# CCM_0010.net
KiCad netlist of a schematic drawn in EAGLE
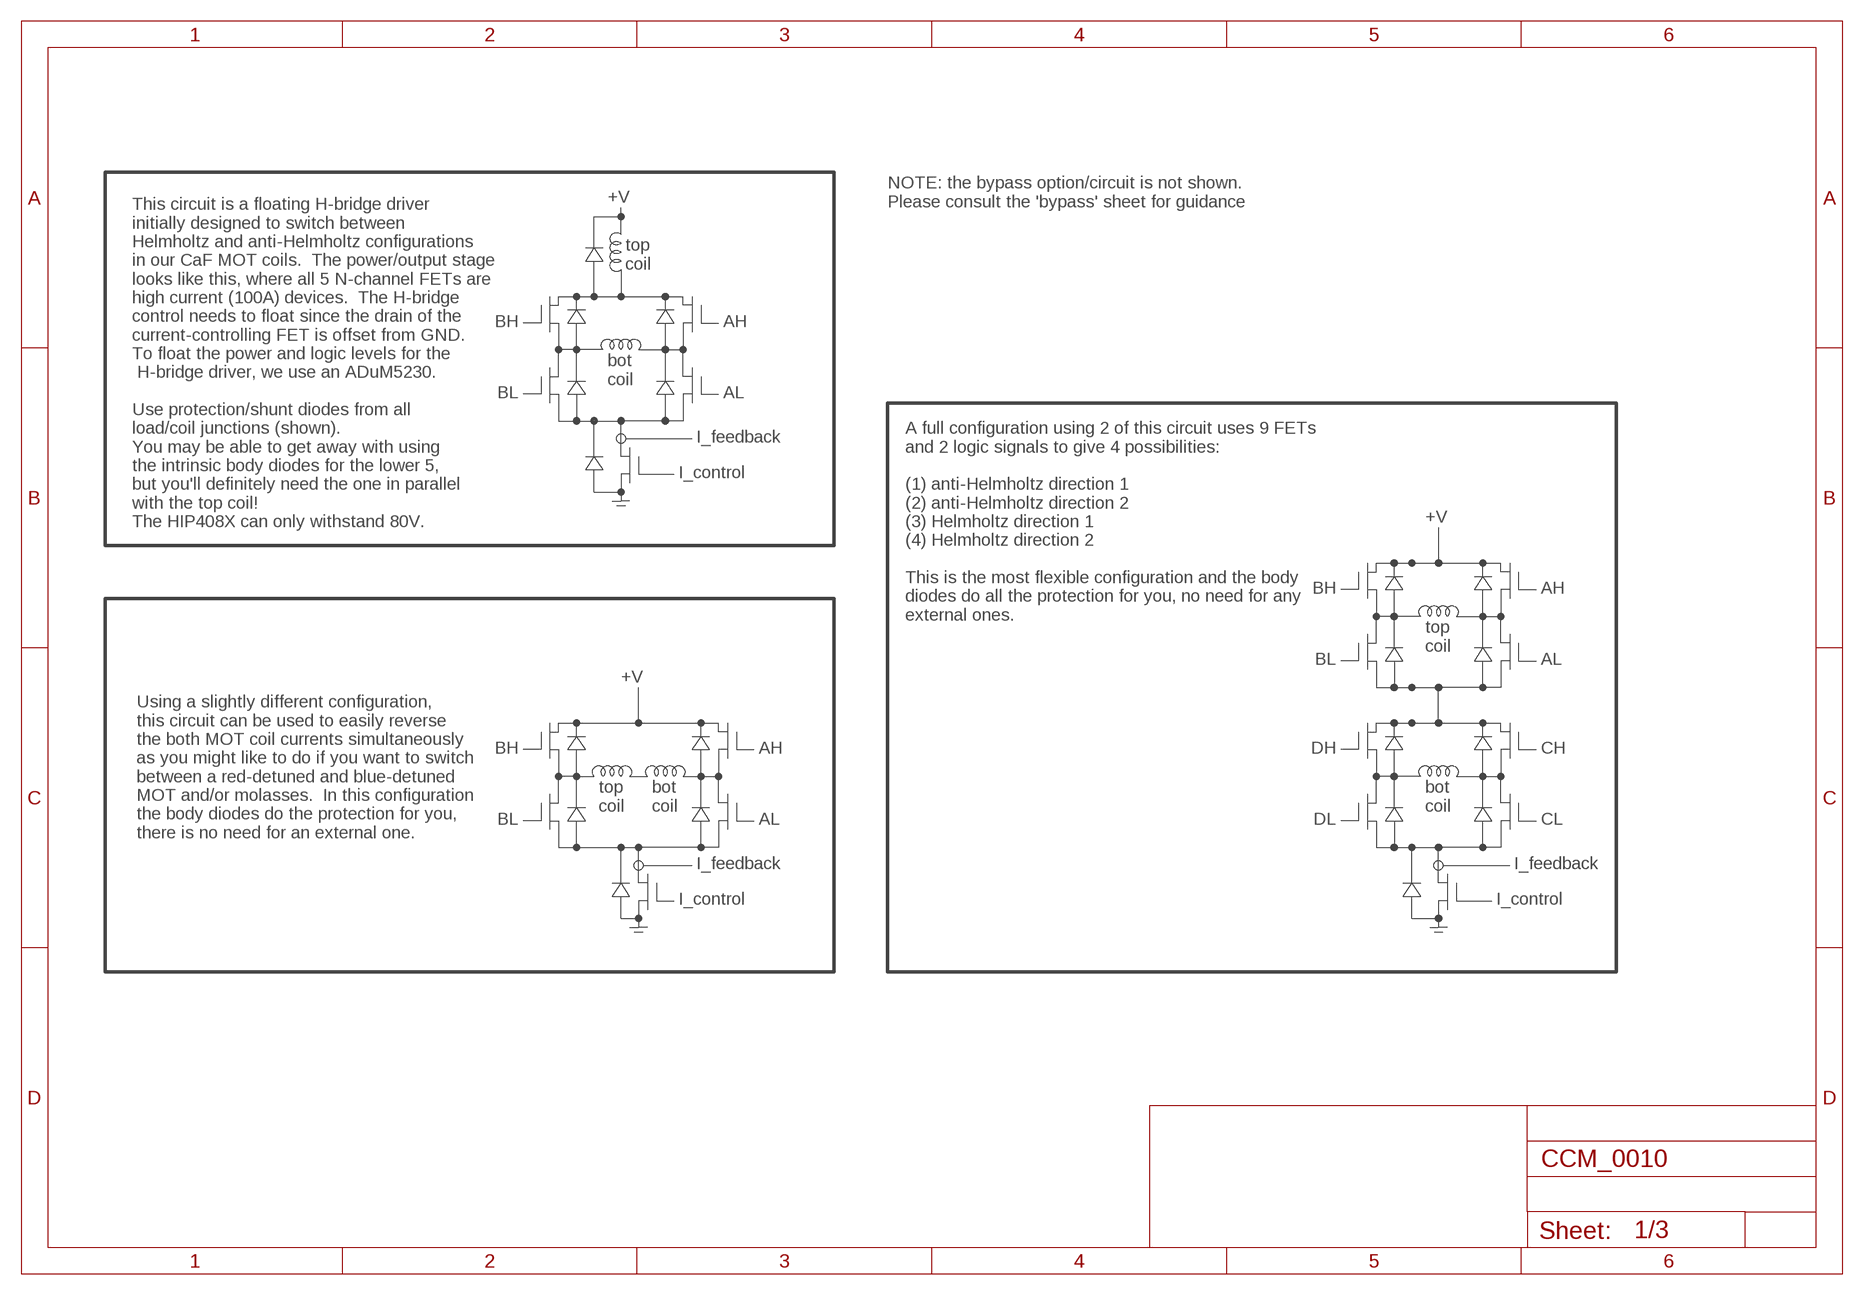
[diagram p0: schematic, sheet 1]
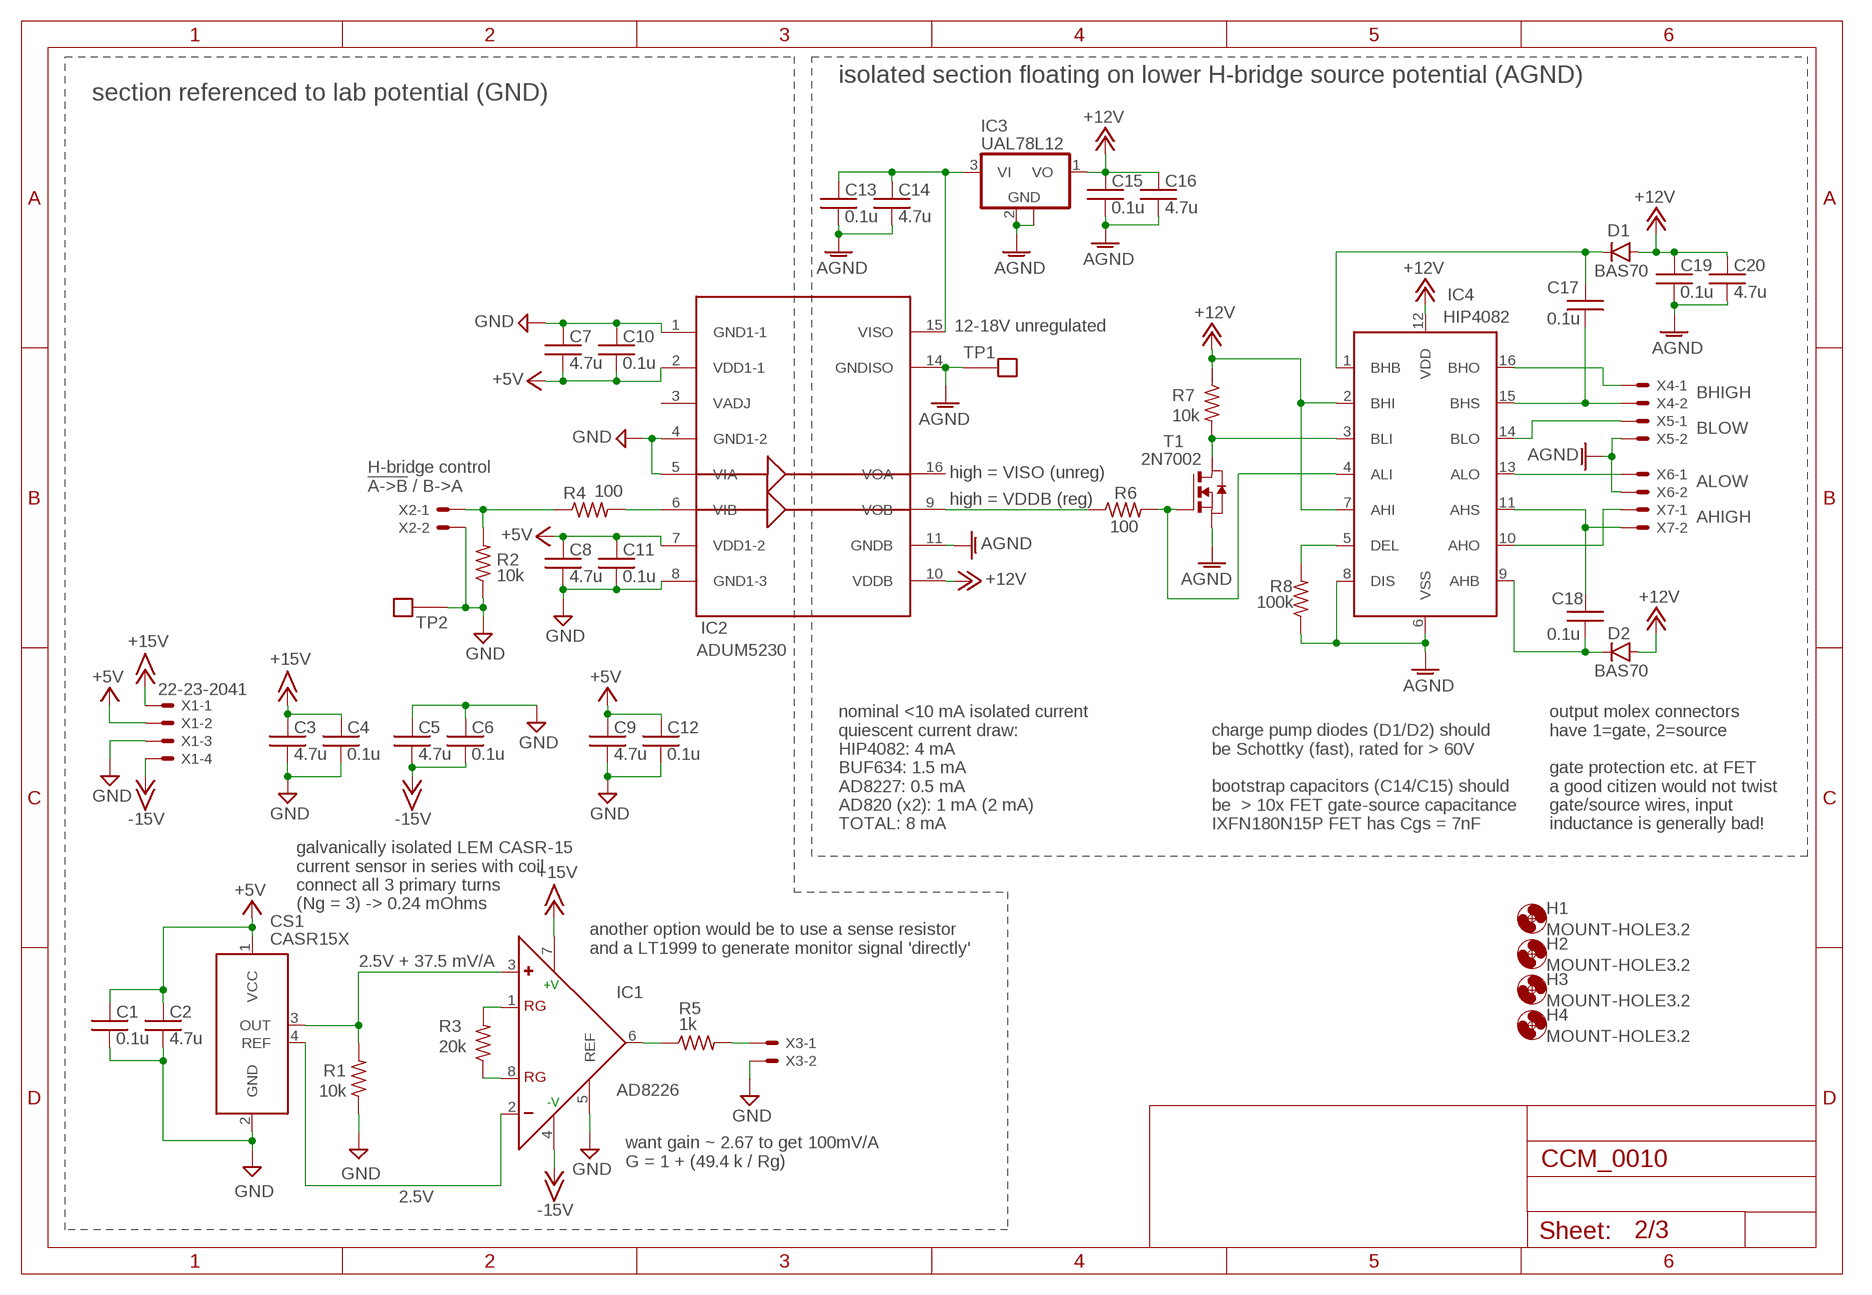
[diagram p1: schematic, sheet 2]
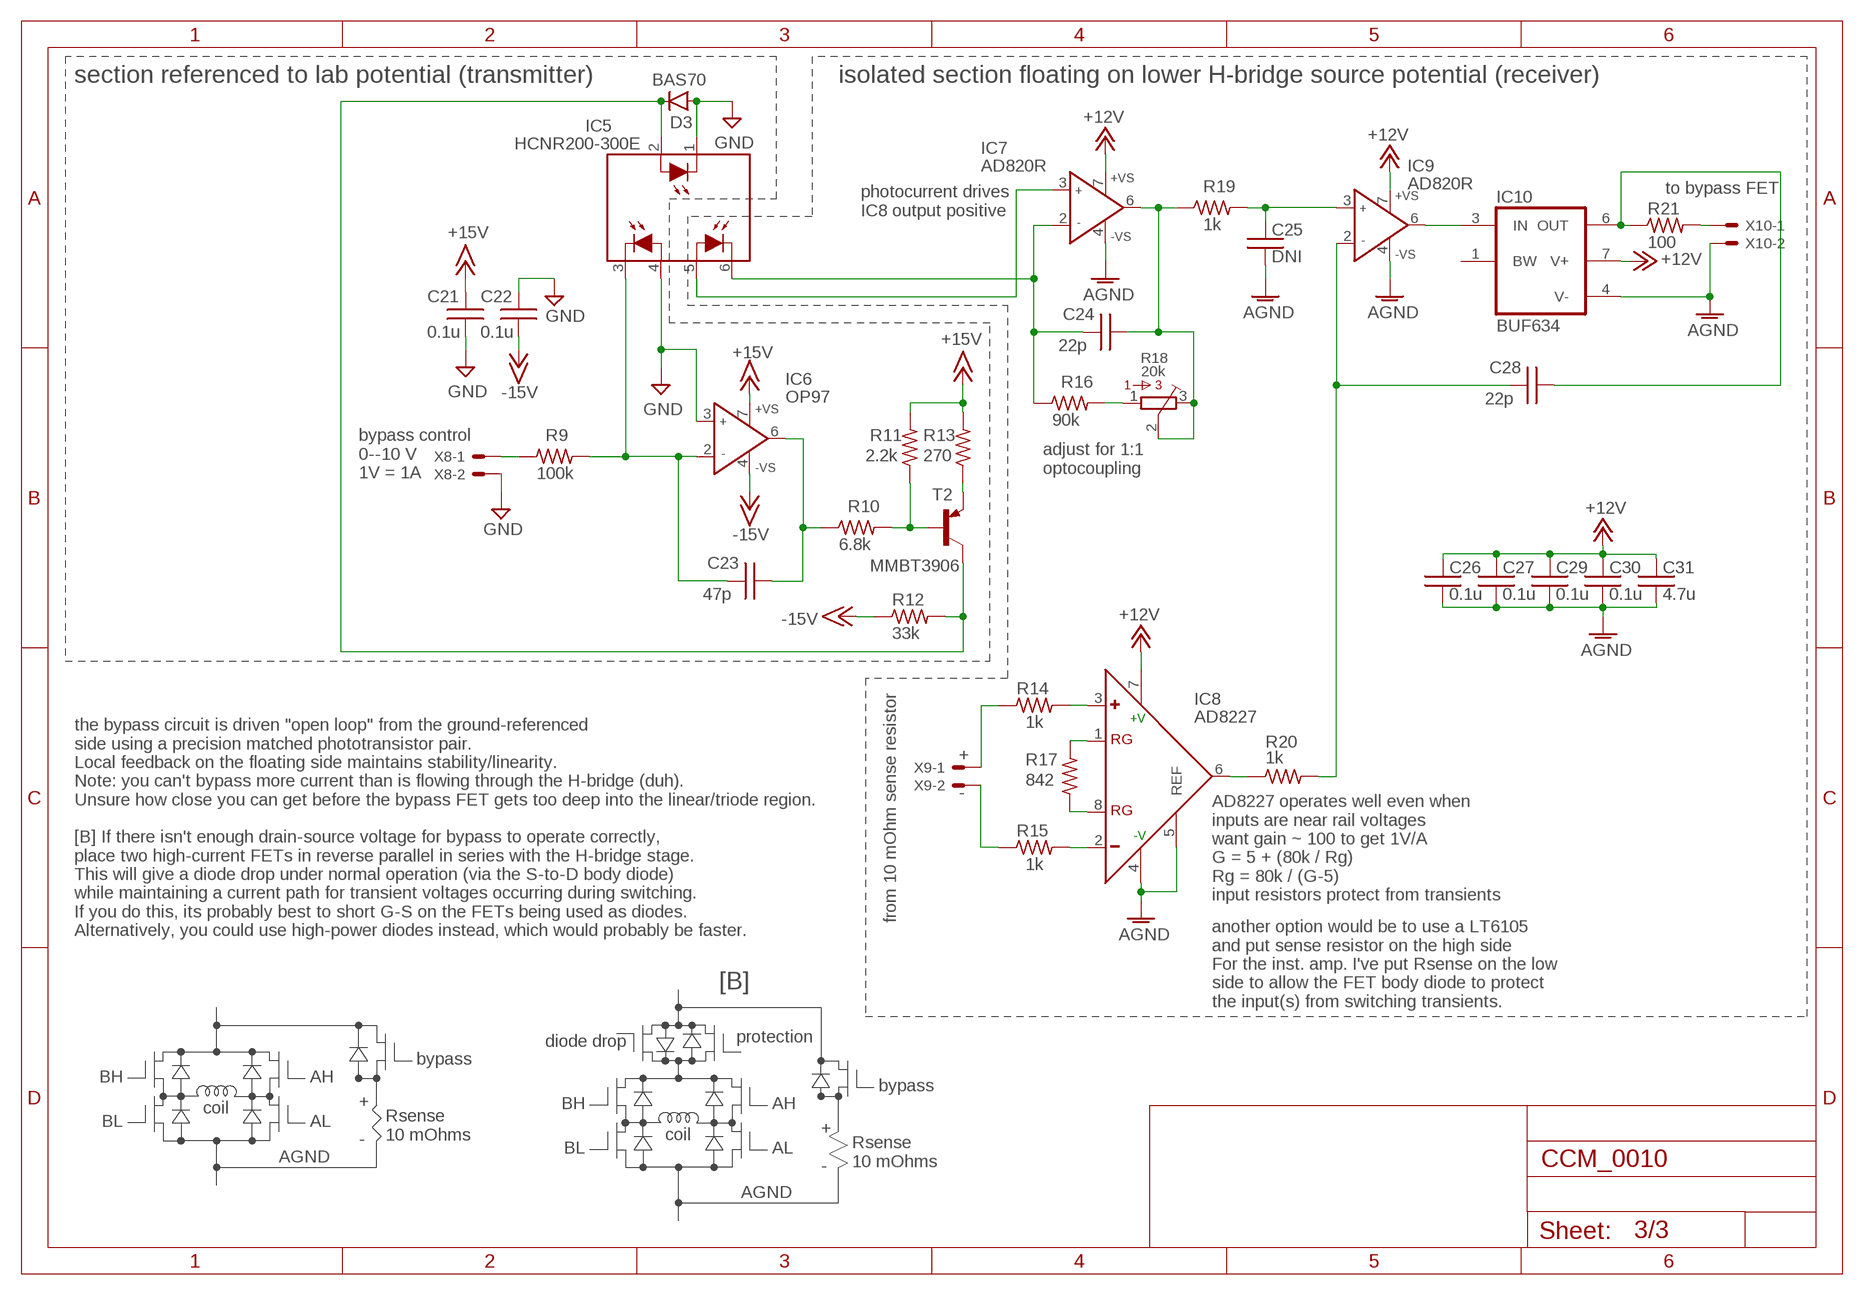
[diagram p2: schematic, sheet 3]

(export (version "E")
  (design (tool "Eeschema 10.0.6"))
  (components
    (comp (ref "C1")
      (value "0.1u")
      (footprint "eagle-import:0603")
      (libsource (lib "eagle-import") (part "C0603"))
    )
    (comp (ref "C2")
      (value "4.7u")
      (footprint "eagle-import:0603")
      (libsource (lib "eagle-import") (part "C0603"))
    )
    (comp (ref "C3")
      (value "4.7u")
      (footprint "eagle-import:0603")
      (libsource (lib "eagle-import") (part "C0603"))
    )
    (comp (ref "C4")
      (value "0.1u")
      (footprint "eagle-import:0603")
      (libsource (lib "eagle-import") (part "C0603"))
    )
    (comp (ref "C5")
      (value "4.7u")
      (footprint "eagle-import:0603")
      (libsource (lib "eagle-import") (part "C0603"))
    )
    (comp (ref "C6")
      (value "0.1u")
      (footprint "eagle-import:0603")
      (libsource (lib "eagle-import") (part "C0603"))
    )
    (comp (ref "C7")
      (value "4.7u")
      (footprint "eagle-import:0603")
      (libsource (lib "eagle-import") (part "C0603"))
    )
    (comp (ref "C8")
      (value "4.7u")
      (footprint "eagle-import:0603")
      (libsource (lib "eagle-import") (part "C0603"))
    )
    (comp (ref "C9")
      (value "4.7u")
      (footprint "eagle-import:0603")
      (libsource (lib "eagle-import") (part "C0603"))
    )
    (comp (ref "C10")
      (value "0.1u")
      (footprint "eagle-import:0603")
      (libsource (lib "eagle-import") (part "C0603"))
    )
    (comp (ref "C11")
      (value "0.1u")
      (footprint "eagle-import:0603")
      (libsource (lib "eagle-import") (part "C0603"))
    )
    (comp (ref "C12")
      (value "0.1u")
      (footprint "eagle-import:0603")
      (libsource (lib "eagle-import") (part "C0603"))
    )
    (comp (ref "C13")
      (value "0.1u")
      (footprint "eagle-import:0603")
      (libsource (lib "eagle-import") (part "C0603"))
    )
    (comp (ref "C14")
      (value "4.7u")
      (footprint "eagle-import:0603")
      (libsource (lib "eagle-import") (part "C0603"))
    )
    (comp (ref "C15")
      (value "0.1u")
      (footprint "eagle-import:0603")
      (libsource (lib "eagle-import") (part "C0603"))
    )
    (comp (ref "C16")
      (value "4.7u")
      (footprint "eagle-import:0603")
      (libsource (lib "eagle-import") (part "C0603"))
    )
    (comp (ref "C17")
      (value "0.1u")
      (footprint "eagle-import:0603")
      (libsource (lib "eagle-import") (part "C0603"))
    )
    (comp (ref "C18")
      (value "0.1u")
      (footprint "eagle-import:0603")
      (libsource (lib "eagle-import") (part "C0603"))
    )
    (comp (ref "C19")
      (value "0.1u")
      (footprint "eagle-import:0603")
      (libsource (lib "eagle-import") (part "C0603"))
    )
    (comp (ref "C20")
      (value "4.7u")
      (footprint "eagle-import:0603")
      (libsource (lib "eagle-import") (part "C0603"))
    )
    (comp (ref "CS1")
      (value "CASR15X")
      (footprint "eagle-import:22-23-2041")
      (libsource (lib "eagle-import") (part "CASR15X"))
    )
    (comp (ref "D1")
      (value "BAS70")
      (footprint "eagle-import:SOT23-3")
      (libsource (lib "eagle-import") (part "DIODESOT23"))
    )
    (comp (ref "D2")
      (value "BAS70")
      (footprint "eagle-import:SOT23-3")
      (libsource (lib "eagle-import") (part "DIODESOT23"))
    )
    (comp (ref "H1")
      (value "MOUNT-HOLE3.2")
      (footprint "eagle-import:3,2")
      (libsource (lib "eagle-import") (part "MOUNT-HOLE3.2"))
    )
    (comp (ref "H2")
      (value "MOUNT-HOLE3.2")
      (footprint "eagle-import:3,2")
      (libsource (lib "eagle-import") (part "MOUNT-HOLE3.2"))
    )
    (comp (ref "H3")
      (value "MOUNT-HOLE3.2")
      (footprint "eagle-import:3,2")
      (libsource (lib "eagle-import") (part "MOUNT-HOLE3.2"))
    )
    (comp (ref "H4")
      (value "MOUNT-HOLE3.2")
      (footprint "eagle-import:3,2")
      (libsource (lib "eagle-import") (part "MOUNT-HOLE3.2"))
    )
    (comp (ref "IC1")
      (value "AD8226")
      (footprint "eagle-import:SO8")
      (fields (field (name "MPN") "AD620AR"))
      (libsource (lib "eagle-import") (part "AD620R"))
    )
    (comp (ref "IC2")
      (value "ADUM5230")
      (footprint "eagle-import:SO16W")
      (libsource (lib "eagle-import") (part "ADUM5230"))
    )
    (comp (ref "IC3")
      (value "UAL78L12")
      (footprint "eagle-import:SOT89")
      (libsource (lib "eagle-import") (part "78LF12"))
    )
    (comp (ref "IC4")
      (value "HIP4082")
      (footprint "eagle-import:SO16")
      (libsource (lib "eagle-import") (part "HIP4082"))
    )
    (comp (ref "R1")
      (value "10k")
      (footprint "eagle-import:0603")
      (libsource (lib "eagle-import") (part "R0603"))
    )
    (comp (ref "R2")
      (value "10k")
      (footprint "eagle-import:0603")
      (libsource (lib "eagle-import") (part "R0603"))
    )
    (comp (ref "R3")
      (value "20k")
      (footprint "eagle-import:0603")
      (libsource (lib "eagle-import") (part "R0603"))
    )
    (comp (ref "R4")
      (value "100")
      (footprint "eagle-import:0603")
      (libsource (lib "eagle-import") (part "R0603"))
    )
    (comp (ref "R5")
      (value "1k")
      (footprint "eagle-import:0603")
      (libsource (lib "eagle-import") (part "R0603"))
    )
    (comp (ref "R6")
      (value "100")
      (footprint "eagle-import:0603")
      (libsource (lib "eagle-import") (part "R0603"))
    )
    (comp (ref "R7")
      (value "10k")
      (footprint "eagle-import:0603")
      (libsource (lib "eagle-import") (part "R0603"))
    )
    (comp (ref "R8")
      (value "100k")
      (footprint "eagle-import:0603")
      (libsource (lib "eagle-import") (part "R0603"))
    )
    (comp (ref "T1")
      (value "2N7002")
      (footprint "eagle-import:SOT-23")
      (libsource (lib "eagle-import") (part "NMOSSOT23"))
    )
    (comp (ref "TP1")
      (value "TESTPOINT")
      (footprint "eagle-import:TESTPOINT")
      (libsource (lib "eagle-import") (part "TESTPOINT"))
    )
    (comp (ref "TP2")
      (value "TESTPOINT")
      (footprint "eagle-import:TESTPOINT")
      (libsource (lib "eagle-import") (part "TESTPOINT"))
    )
    (comp (ref "X1")
      (value "22-23-2041")
      (footprint "eagle-import:22-23-2041")
      (fields (field (name "MF") "MOLEX"))
      (libsource (lib "eagle-import") (part "22-23-2041"))
    )
    (comp (ref "X2")
      (value "22-23-2021")
      (footprint "eagle-import:22-23-2021")
      (fields (field (name "MF") "MOLEX"))
      (libsource (lib "eagle-import") (part "22-23-2021"))
    )
    (comp (ref "X3")
      (value "22-23-2021")
      (footprint "eagle-import:22-23-2021")
      (fields (field (name "MF") "MOLEX"))
      (libsource (lib "eagle-import") (part "22-23-2021"))
    )
    (comp (ref "X4")
      (value "22-23-2021")
      (footprint "eagle-import:22-23-2021")
      (fields (field (name "MF") "MOLEX"))
      (libsource (lib "eagle-import") (part "22-23-2021"))
    )
    (comp (ref "X5")
      (value "22-23-2021")
      (footprint "eagle-import:22-23-2021")
      (fields (field (name "MF") "MOLEX"))
      (libsource (lib "eagle-import") (part "22-23-2021"))
    )
    (comp (ref "X6")
      (value "22-23-2021")
      (footprint "eagle-import:22-23-2021")
      (fields (field (name "MF") "MOLEX"))
      (libsource (lib "eagle-import") (part "22-23-2021"))
    )
    (comp (ref "X7")
      (value "22-23-2021")
      (footprint "eagle-import:22-23-2021")
      (fields (field (name "MF") "MOLEX"))
      (libsource (lib "eagle-import") (part "22-23-2021"))
    )
    (comp (ref "C21")
      (value "0.1u")
      (footprint "eagle-import:0603")
      (libsource (lib "eagle-import") (part "C0603"))
    )
    (comp (ref "C22")
      (value "0.1u")
      (footprint "eagle-import:0603")
      (libsource (lib "eagle-import") (part "C0603"))
    )
    (comp (ref "C23")
      (value "47p")
      (footprint "eagle-import:0603")
      (libsource (lib "eagle-import") (part "C0603"))
    )
    (comp (ref "C24")
      (value "22p")
      (footprint "eagle-import:0603")
      (libsource (lib "eagle-import") (part "C0603"))
    )
    (comp (ref "C25")
      (value "DNI")
      (footprint "eagle-import:0603")
      (libsource (lib "eagle-import") (part "C0603"))
    )
    (comp (ref "C26")
      (value "0.1u")
      (footprint "eagle-import:0603")
      (libsource (lib "eagle-import") (part "C0603"))
    )
    (comp (ref "C27")
      (value "0.1u")
      (footprint "eagle-import:0603")
      (libsource (lib "eagle-import") (part "C0603"))
    )
    (comp (ref "C28")
      (value "22p")
      (footprint "eagle-import:0603")
      (libsource (lib "eagle-import") (part "C0603"))
    )
    (comp (ref "C29")
      (value "0.1u")
      (footprint "eagle-import:0603")
      (libsource (lib "eagle-import") (part "C0603"))
    )
    (comp (ref "C30")
      (value "0.1u")
      (footprint "eagle-import:0603")
      (libsource (lib "eagle-import") (part "C0603"))
    )
    (comp (ref "C31")
      (value "4.7u")
      (footprint "eagle-import:0603")
      (libsource (lib "eagle-import") (part "C0603"))
    )
    (comp (ref "D3")
      (value "BAS70")
      (footprint "eagle-import:SOT23-3")
      (libsource (lib "eagle-import") (part "DIODESOT23"))
    )
    (comp (ref "IC5")
      (value "HCNR200-300E")
      (footprint "eagle-import:DIP8-400")
      (libsource (lib "eagle-import") (part "HCNR20-300E0"))
    )
    (comp (ref "IC6")
      (value "OP97")
      (footprint "eagle-import:SO8")
      (fields (field (name "MF") "ALTERA CORPORATION") (field (name "MPN") "AD825ARZ"))
      (libsource (lib "eagle-import") (part "AD825R"))
    )
    (comp (ref "IC7")
      (value "AD820R")
      (footprint "eagle-import:SO8")
      (libsource (lib "eagle-import") (part "AD820R"))
    )
    (comp (ref "IC8")
      (value "AD8227")
      (footprint "eagle-import:SO8")
      (fields (field (name "MPN") "AD620AR"))
      (libsource (lib "eagle-import") (part "AD620R"))
    )
    (comp (ref "IC9")
      (value "AD820R")
      (footprint "eagle-import:SO8")
      (libsource (lib "eagle-import") (part "AD820R"))
    )
    (comp (ref "IC10")
      (value "BUF634")
      (footprint "eagle-import:SO8")
      (libsource (lib "eagle-import") (part "BUF634"))
    )
    (comp (ref "R9")
      (value "100k")
      (footprint "eagle-import:0603")
      (libsource (lib "eagle-import") (part "R0603"))
    )
    (comp (ref "R10")
      (value "6.8k")
      (footprint "eagle-import:0603")
      (libsource (lib "eagle-import") (part "R0603"))
    )
    (comp (ref "R11")
      (value "2.2k")
      (footprint "eagle-import:0603")
      (libsource (lib "eagle-import") (part "R0603"))
    )
    (comp (ref "R12")
      (value "33k")
      (footprint "eagle-import:0603")
      (libsource (lib "eagle-import") (part "R0603"))
    )
    (comp (ref "R13")
      (value "270")
      (footprint "eagle-import:0603")
      (libsource (lib "eagle-import") (part "R0603"))
    )
    (comp (ref "R14")
      (value "1k")
      (footprint "eagle-import:0603")
      (libsource (lib "eagle-import") (part "R0603"))
    )
    (comp (ref "R15")
      (value "1k")
      (footprint "eagle-import:0603")
      (libsource (lib "eagle-import") (part "R0603"))
    )
    (comp (ref "R16")
      (value "90k")
      (footprint "eagle-import:0603")
      (libsource (lib "eagle-import") (part "R0603"))
    )
    (comp (ref "R17")
      (value "842")
      (footprint "eagle-import:0603")
      (libsource (lib "eagle-import") (part "R0603"))
    )
    (comp (ref "R18")
      (value "20k")
      (footprint "eagle-import:3386W")
      (libsource (lib "eagle-import") (part "3386-W"))
    )
    (comp (ref "R19")
      (value "1k")
      (footprint "eagle-import:0603")
      (libsource (lib "eagle-import") (part "R0603"))
    )
    (comp (ref "R20")
      (value "1k")
      (footprint "eagle-import:0603")
      (libsource (lib "eagle-import") (part "R0603"))
    )
    (comp (ref "R21")
      (value "100")
      (footprint "eagle-import:0603")
      (libsource (lib "eagle-import") (part "R0603"))
    )
    (comp (ref "T2")
      (value "MMBT3906")
      (footprint "eagle-import:SOT23-BEC")
      (libsource (lib "eagle-import") (part "-PNP-SOT23-BECMMBT3906LT1"))
    )
    (comp (ref "X8")
      (value "22-23-2021")
      (footprint "eagle-import:22-23-2021")
      (fields (field (name "MF") "MOLEX"))
      (libsource (lib "eagle-import") (part "22-23-2021"))
    )
    (comp (ref "X9")
      (value "22-23-2021")
      (footprint "eagle-import:22-23-2021")
      (fields (field (name "MF") "MOLEX"))
      (libsource (lib "eagle-import") (part "22-23-2021"))
    )
    (comp (ref "X10")
      (value "22-23-2021")
      (footprint "eagle-import:22-23-2021")
      (fields (field (name "MF") "MOLEX"))
      (libsource (lib "eagle-import") (part "22-23-2021"))
    )
  )
  (nets
    (net (code "1") (name "+5V") (class "Default")
      (node (ref "C1") (pin "1") (pinfunction "1_1") (pintype "passive"))
      (node (ref "C10") (pin "2") (pinfunction "2_2") (pintype "passive"))
      (node (ref "C11") (pin "1") (pinfunction "1_1") (pintype "passive"))
      (node (ref "C12") (pin "1") (pinfunction "1_1") (pintype "passive"))
      (node (ref "C2") (pin "1") (pinfunction "1_1") (pintype "passive"))
      (node (ref "C7") (pin "2") (pinfunction "2_2") (pintype "passive"))
      (node (ref "C8") (pin "1") (pinfunction "1_1") (pintype "passive"))
      (node (ref "C9") (pin "1") (pinfunction "1_1") (pintype "passive"))
      (node (ref "CS1") (pin "1") (pinfunction "VCC_1") (pintype "bidirectional"))
      (node (ref "IC2") (pin "2") (pinfunction "VDD1-1_2") (pintype "bidirectional"))
      (node (ref "IC2") (pin "7") (pinfunction "VDD1-2_7") (pintype "bidirectional"))
      (node (ref "X1") (pin "2") (pinfunction "S_2") (pintype "passive"))
    )
    (net (code "2") (name "+12V") (class "Default")
      (node (ref "C15") (pin "1") (pinfunction "1_1") (pintype "passive"))
      (node (ref "C16") (pin "1") (pinfunction "1_1") (pintype "passive"))
      (node (ref "C19") (pin "1") (pinfunction "1_1") (pintype "passive"))
      (node (ref "C20") (pin "1") (pinfunction "1_1") (pintype "passive"))
      (node (ref "C26") (pin "1") (pinfunction "1_1") (pintype "passive"))
      (node (ref "C27") (pin "1") (pinfunction "1_1") (pintype "passive"))
      (node (ref "C29") (pin "1") (pinfunction "1_1") (pintype "passive"))
      (node (ref "C30") (pin "1") (pinfunction "1_1") (pintype "passive"))
      (node (ref "C31") (pin "1") (pinfunction "1_1") (pintype "passive"))
      (node (ref "D1") (pin "1") (pinfunction "A_1") (pintype "passive"))
      (node (ref "D2") (pin "1") (pinfunction "A_1") (pintype "passive"))
      (node (ref "IC10") (pin "7") (pinfunction "V+_7") (pintype "power_in"))
      (node (ref "IC2") (pin "10") (pinfunction "VDDB_10") (pintype "bidirectional"))
      (node (ref "IC3") (pin "1") (pinfunction "VO_1") (pintype "passive"))
      (node (ref "IC4") (pin "12") (pinfunction "VDD_12") (pintype "power_in"))
      (node (ref "IC4") (pin "2") (pinfunction "BHI_2") (pintype "input"))
      (node (ref "IC4") (pin "7") (pinfunction "AHI_7") (pintype "input"))
      (node (ref "IC7") (pin "7") (pinfunction "+VS_7") (pintype "input"))
      (node (ref "IC8") (pin "7") (pinfunction "+V_7") (pintype "power_in"))
      (node (ref "IC9") (pin "7") (pinfunction "+VS_7") (pintype "input"))
      (node (ref "R7") (pin "1") (pinfunction "1_1") (pintype "passive"))
    )
    (net (code "3") (name "+15V") (class "Default")
      (node (ref "C21") (pin "2") (pinfunction "2_2") (pintype "passive"))
      (node (ref "C3") (pin "1") (pinfunction "1_1") (pintype "passive"))
      (node (ref "C4") (pin "1") (pinfunction "1_1") (pintype "passive"))
      (node (ref "IC1") (pin "7") (pinfunction "+V_7") (pintype "power_in"))
      (node (ref "IC6") (pin "7") (pinfunction "+VS_7") (pintype "input"))
      (node (ref "R11") (pin "2") (pinfunction "2_2") (pintype "passive"))
      (node (ref "R13") (pin "2") (pinfunction "2_2") (pintype "passive"))
      (node (ref "X1") (pin "1") (pinfunction "S_1") (pintype "passive"))
    )
    (net (code "4") (name "-15V") (class "Default")
      (node (ref "C22") (pin "1") (pinfunction "1_1") (pintype "passive"))
      (node (ref "C5") (pin "2") (pinfunction "2_2") (pintype "passive"))
      (node (ref "C6") (pin "2") (pinfunction "2_2") (pintype "passive"))
      (node (ref "IC1") (pin "4") (pinfunction "-V_4") (pintype "power_in"))
      (node (ref "IC6") (pin "4") (pinfunction "-VS_4") (pintype "input"))
      (node (ref "R12") (pin "1") (pinfunction "1_1") (pintype "passive"))
      (node (ref "X1") (pin "4") (pinfunction "S_4") (pintype "passive"))
    )
    (net (code "5") (name "AGND") (class "Default")
      (node (ref "C13") (pin "2") (pinfunction "2_2") (pintype "passive"))
      (node (ref "C14") (pin "2") (pinfunction "2_2") (pintype "passive"))
      (node (ref "C15") (pin "2") (pinfunction "2_2") (pintype "passive"))
      (node (ref "C16") (pin "2") (pinfunction "2_2") (pintype "passive"))
      (node (ref "C19") (pin "2") (pinfunction "2_2") (pintype "passive"))
      (node (ref "C20") (pin "2") (pinfunction "2_2") (pintype "passive"))
      (node (ref "C25") (pin "2") (pinfunction "2_2") (pintype "passive"))
      (node (ref "C26") (pin "2") (pinfunction "2_2") (pintype "passive"))
      (node (ref "C27") (pin "2") (pinfunction "2_2") (pintype "passive"))
      (node (ref "C29") (pin "2") (pinfunction "2_2") (pintype "passive"))
      (node (ref "C30") (pin "2") (pinfunction "2_2") (pintype "passive"))
      (node (ref "C31") (pin "2") (pinfunction "2_2") (pintype "passive"))
      (node (ref "IC10") (pin "4") (pinfunction "V-_4") (pintype "power_in"))
      (node (ref "IC2") (pin "11") (pinfunction "GNDB_11") (pintype "bidirectional"))
      (node (ref "IC2") (pin "14") (pinfunction "GNDISO_14") (pintype "bidirectional"))
      (node (ref "IC3") (pin "2") (pinfunction "GND_2") (pintype "passive"))
      (node (ref "IC3") (pin "2@1") (pinfunction "GND_2@1") (pintype "passive"))
      (node (ref "IC4") (pin "6") (pinfunction "VSS_6") (pintype "power_in"))
      (node (ref "IC4") (pin "8") (pinfunction "DIS_8") (pintype "input"))
      (node (ref "IC7") (pin "4") (pinfunction "-VS_4") (pintype "input"))
      (node (ref "IC8") (pin "4") (pinfunction "-V_4") (pintype "power_in"))
      (node (ref "IC8") (pin "5") (pinfunction "REF_5") (pintype "passive"))
      (node (ref "IC9") (pin "4") (pinfunction "-VS_4") (pintype "input"))
      (node (ref "R8") (pin "1") (pinfunction "1_1") (pintype "passive"))
      (node (ref "T1") (pin "2") (pinfunction "S_2") (pintype "passive"))
      (node (ref "TP1") (pin "P$1") (pinfunction "P$1_P$1") (pintype "bidirectional"))
      (node (ref "X10") (pin "2") (pinfunction "S_2") (pintype "passive"))
      (node (ref "X5") (pin "2") (pinfunction "S_2") (pintype "passive"))
      (node (ref "X6") (pin "2") (pinfunction "S_2") (pintype "passive"))
    )
    (net (code "6") (name "GND") (class "Default")
      (node (ref "C1") (pin "2") (pinfunction "2_2") (pintype "passive"))
      (node (ref "C10") (pin "1") (pinfunction "1_1") (pintype "passive"))
      (node (ref "C11") (pin "2") (pinfunction "2_2") (pintype "passive"))
      (node (ref "C12") (pin "2") (pinfunction "2_2") (pintype "passive"))
      (node (ref "C2") (pin "2") (pinfunction "2_2") (pintype "passive"))
      (node (ref "C21") (pin "1") (pinfunction "1_1") (pintype "passive"))
      (node (ref "C22") (pin "2") (pinfunction "2_2") (pintype "passive"))
      (node (ref "C3") (pin "2") (pinfunction "2_2") (pintype "passive"))
      (node (ref "C4") (pin "2") (pinfunction "2_2") (pintype "passive"))
      (node (ref "C5") (pin "1") (pinfunction "1_1") (pintype "passive"))
      (node (ref "C6") (pin "1") (pinfunction "1_1") (pintype "passive"))
      (node (ref "C7") (pin "1") (pinfunction "1_1") (pintype "passive"))
      (node (ref "C8") (pin "2") (pinfunction "2_2") (pintype "passive"))
      (node (ref "C9") (pin "2") (pinfunction "2_2") (pintype "passive"))
      (node (ref "CS1") (pin "2") (pinfunction "GND_2") (pintype "bidirectional"))
      (node (ref "D3") (pin "1") (pinfunction "A_1") (pintype "passive"))
      (node (ref "IC1") (pin "5") (pinfunction "REF_5") (pintype "passive"))
      (node (ref "IC2") (pin "1") (pinfunction "GND1-1_1") (pintype "bidirectional"))
      (node (ref "IC2") (pin "4") (pinfunction "GND1-2_4") (pintype "bidirectional"))
      (node (ref "IC2") (pin "5") (pinfunction "VIA_5") (pintype "bidirectional"))
      (node (ref "IC2") (pin "8") (pinfunction "GND1-3_8") (pintype "bidirectional"))
      (node (ref "IC5") (pin "1") (pinfunction "C_1") (pintype "passive"))
      (node (ref "IC5") (pin "4") (pinfunction "A1_4") (pintype "passive"))
      (node (ref "IC6") (pin "3") (pinfunction "IN+_3") (pintype "input"))
      (node (ref "R1") (pin "1") (pinfunction "1_1") (pintype "passive"))
      (node (ref "R2") (pin "1") (pinfunction "1_1") (pintype "passive"))
      (node (ref "TP2") (pin "P$1") (pinfunction "P$1_P$1") (pintype "bidirectional"))
      (node (ref "X1") (pin "3") (pinfunction "S_3") (pintype "passive"))
      (node (ref "X2") (pin "2") (pinfunction "S_2") (pintype "passive"))
      (node (ref "X3") (pin "2") (pinfunction "S_2") (pintype "passive"))
      (node (ref "X8") (pin "2") (pinfunction "S_2") (pintype "passive"))
    )
    (net (code "7") (name "Net-(CS1-OUT)") (class "Default")
      (node (ref "CS1") (pin "3") (pinfunction "OUT_3") (pintype "bidirectional"))
      (node (ref "IC1") (pin "3") (pinfunction "+_3") (pintype "input"))
      (node (ref "R1") (pin "2") (pinfunction "2_2") (pintype "passive"))
    )
    (net (code "8") (name "Net-(CS1-REF)") (class "Default")
      (node (ref "CS1") (pin "4") (pinfunction "REF_4") (pintype "bidirectional"))
      (node (ref "IC1") (pin "2") (pinfunction "-_2") (pintype "input"))
    )
    (net (code "9") (name "Net-(D1-C)") (class "Default")
      (node (ref "C17") (pin "2") (pinfunction "2_2") (pintype "passive"))
      (node (ref "D1") (pin "3") (pinfunction "C_3") (pintype "passive"))
      (node (ref "IC4") (pin "1") (pinfunction "BHB_1") (pintype "input"))
    )
    (net (code "10") (name "Net-(D2-C)") (class "Default")
      (node (ref "C18") (pin "1") (pinfunction "1_1") (pintype "passive"))
      (node (ref "D2") (pin "3") (pinfunction "C_3") (pintype "passive"))
      (node (ref "IC4") (pin "9") (pinfunction "AHB_9") (pintype "output"))
    )
    (net (code "11") (name "Net-(D3-C)") (class "Default")
      (node (ref "D3") (pin "3") (pinfunction "C_3") (pintype "passive"))
      (node (ref "IC5") (pin "2") (pinfunction "A_2") (pintype "passive"))
      (node (ref "R12") (pin "2") (pinfunction "2_2") (pintype "passive"))
      (node (ref "T2") (pin "C") (pinfunction "C_C") (pintype "passive"))
    )
    (net (code "12") (name "Net-(IC1-OUT)") (class "Default")
      (node (ref "IC1") (pin "6") (pinfunction "OUT_6") (pintype "output"))
      (node (ref "R5") (pin "1") (pinfunction "1_1") (pintype "passive"))
    )
    (net (code "13") (name "Net-(IC1-RG-Pad1)") (class "Default")
      (node (ref "IC1") (pin "1") (pinfunction "RG_1") (pintype "passive"))
      (node (ref "R3") (pin "2") (pinfunction "2_2") (pintype "passive"))
    )
    (net (code "14") (name "Net-(IC1-RG-Pad8)") (class "Default")
      (node (ref "IC1") (pin "8") (pinfunction "RG_8") (pintype "passive"))
      (node (ref "R3") (pin "1") (pinfunction "1_1") (pintype "passive"))
    )
    (net (code "15") (name "Net-(IC2-VIB)") (class "Default")
      (node (ref "IC2") (pin "6") (pinfunction "VIB_6") (pintype "bidirectional"))
      (node (ref "R4") (pin "2") (pinfunction "2_2") (pintype "passive"))
    )
    (net (code "16") (name "Net-(IC2-VISO)") (class "Default")
      (node (ref "C13") (pin "1") (pinfunction "1_1") (pintype "passive"))
      (node (ref "C14") (pin "1") (pinfunction "1_1") (pintype "passive"))
      (node (ref "IC2") (pin "15") (pinfunction "VISO_15") (pintype "bidirectional"))
      (node (ref "IC3") (pin "3") (pinfunction "VI_3") (pintype "input"))
    )
    (net (code "17") (name "Net-(IC2-VOB)") (class "Default")
      (node (ref "IC2") (pin "9") (pinfunction "VOB_9") (pintype "bidirectional"))
      (node (ref "R6") (pin "1") (pinfunction "1_1") (pintype "passive"))
    )
    (net (code "18") (name "Net-(IC4-AHO)") (class "Default")
      (node (ref "IC4") (pin "10") (pinfunction "AHO_10") (pintype "input"))
      (node (ref "X7") (pin "1") (pinfunction "S_1") (pintype "passive"))
    )
    (net (code "19") (name "Net-(IC4-AHS)") (class "Default")
      (node (ref "C18") (pin "2") (pinfunction "2_2") (pintype "passive"))
      (node (ref "IC4") (pin "11") (pinfunction "AHS_11") (pintype "output"))
      (node (ref "X7") (pin "2") (pinfunction "S_2") (pintype "passive"))
    )
    (net (code "20") (name "Net-(IC4-ALI)") (class "Default")
      (node (ref "IC4") (pin "4") (pinfunction "ALI_4") (pintype "input"))
      (node (ref "R6") (pin "2") (pinfunction "2_2") (pintype "passive"))
      (node (ref "T1") (pin "3") (pinfunction "G_3") (pintype "passive"))
    )
    (net (code "21") (name "Net-(IC4-ALO)") (class "Default")
      (node (ref "IC4") (pin "13") (pinfunction "ALO_13") (pintype "passive"))
      (node (ref "X6") (pin "1") (pinfunction "S_1") (pintype "passive"))
    )
    (net (code "22") (name "Net-(IC4-BHO)") (class "Default")
      (node (ref "IC4") (pin "16") (pinfunction "BHO_16") (pintype "output"))
      (node (ref "X4") (pin "1") (pinfunction "S_1") (pintype "passive"))
    )
    (net (code "23") (name "Net-(IC4-BHS)") (class "Default")
      (node (ref "C17") (pin "1") (pinfunction "1_1") (pintype "passive"))
      (node (ref "IC4") (pin "15") (pinfunction "BHS_15") (pintype "input"))
      (node (ref "X4") (pin "2") (pinfunction "S_2") (pintype "passive"))
    )
    (net (code "24") (name "Net-(IC4-BLI)") (class "Default")
      (node (ref "IC4") (pin "3") (pinfunction "BLI_3") (pintype "input"))
      (node (ref "R7") (pin "2") (pinfunction "2_2") (pintype "passive"))
      (node (ref "T1") (pin "1") (pinfunction "D_1") (pintype "passive"))
    )
    (net (code "25") (name "Net-(IC4-BLO)") (class "Default")
      (node (ref "IC4") (pin "14") (pinfunction "BLO_14") (pintype "output"))
      (node (ref "X5") (pin "1") (pinfunction "S_1") (pintype "passive"))
    )
    (net (code "26") (name "Net-(IC4-DEL)") (class "Default")
      (node (ref "IC4") (pin "5") (pinfunction "DEL_5") (pintype "input"))
      (node (ref "R8") (pin "2") (pinfunction "2_2") (pintype "passive"))
    )
    (net (code "27") (name "Net-(IC5-A2)") (class "Default")
      (node (ref "IC5") (pin "5") (pinfunction "A2_5") (pintype "passive"))
      (node (ref "IC7") (pin "3") (pinfunction "IN+_3") (pintype "input"))
    )
    (net (code "28") (name "Net-(IC5-C1)") (class "Default")
      (node (ref "C23") (pin "2") (pinfunction "2_2") (pintype "passive"))
      (node (ref "IC5") (pin "3") (pinfunction "C1_3") (pintype "passive"))
      (node (ref "IC6") (pin "2") (pinfunction "IN-_2") (pintype "input"))
      (node (ref "R9") (pin "2") (pinfunction "2_2") (pintype "passive"))
    )
    (net (code "29") (name "Net-(IC5-C2)") (class "Default")
      (node (ref "C24") (pin "2") (pinfunction "2_2") (pintype "passive"))
      (node (ref "IC5") (pin "6") (pinfunction "C2_6") (pintype "passive"))
      (node (ref "IC7") (pin "2") (pinfunction "IN-_2") (pintype "input"))
      (node (ref "R16") (pin "1") (pinfunction "1_1") (pintype "passive"))
    )
    (net (code "30") (name "Net-(IC6-OUT)") (class "Default")
      (node (ref "C23") (pin "1") (pinfunction "1_1") (pintype "passive"))
      (node (ref "IC6") (pin "6") (pinfunction "OUT_6") (pintype "output"))
      (node (ref "R10") (pin "1") (pinfunction "1_1") (pintype "passive"))
    )
    (net (code "31") (name "Net-(IC7-OUT)") (class "Default")
      (node (ref "C24") (pin "1") (pinfunction "1_1") (pintype "passive"))
      (node (ref "IC7") (pin "6") (pinfunction "OUT_6") (pintype "output"))
      (node (ref "R18") (pin "2") (pinfunction "2_2") (pintype "passive"))
      (node (ref "R18") (pin "3") (pinfunction "3_3") (pintype "passive"))
      (node (ref "R19") (pin "1") (pinfunction "1_1") (pintype "passive"))
    )
    (net (code "32") (name "Net-(IC8-+)") (class "Default")
      (node (ref "IC8") (pin "3") (pinfunction "+_3") (pintype "input"))
      (node (ref "R14") (pin "2") (pinfunction "2_2") (pintype "passive"))
    )
    (net (code "33") (name "Net-(IC8--)") (class "Default")
      (node (ref "IC8") (pin "2") (pinfunction "-_2") (pintype "input"))
      (node (ref "R15") (pin "2") (pinfunction "2_2") (pintype "passive"))
    )
    (net (code "34") (name "Net-(IC8-OUT)") (class "Default")
      (node (ref "IC8") (pin "6") (pinfunction "OUT_6") (pintype "output"))
      (node (ref "R20") (pin "1") (pinfunction "1_1") (pintype "passive"))
    )
    (net (code "35") (name "Net-(IC8-RG-Pad1)") (class "Default")
      (node (ref "IC8") (pin "1") (pinfunction "RG_1") (pintype "passive"))
      (node (ref "R17") (pin "2") (pinfunction "2_2") (pintype "passive"))
    )
    (net (code "36") (name "Net-(IC8-RG-Pad8)") (class "Default")
      (node (ref "IC8") (pin "8") (pinfunction "RG_8") (pintype "passive"))
      (node (ref "R17") (pin "1") (pinfunction "1_1") (pintype "passive"))
    )
    (net (code "37") (name "Net-(IC9-IN+)") (class "Default")
      (node (ref "C25") (pin "1") (pinfunction "1_1") (pintype "passive"))
      (node (ref "IC9") (pin "3") (pinfunction "IN+_3") (pintype "input"))
      (node (ref "R19") (pin "2") (pinfunction "2_2") (pintype "passive"))
    )
    (net (code "38") (name "Net-(IC9-IN-)") (class "Default")
      (node (ref "C28") (pin "2") (pinfunction "2_2") (pintype "passive"))
      (node (ref "IC9") (pin "2") (pinfunction "IN-_2") (pintype "input"))
      (node (ref "R20") (pin "2") (pinfunction "2_2") (pintype "passive"))
    )
    (net (code "39") (name "Net-(IC10-IN)") (class "Default")
      (node (ref "IC10") (pin "3") (pinfunction "IN_3") (pintype "input"))
      (node (ref "IC9") (pin "6") (pinfunction "OUT_6") (pintype "output"))
    )
    (net (code "40") (name "Net-(IC10-OUT)") (class "Default")
      (node (ref "C28") (pin "1") (pinfunction "1_1") (pintype "passive"))
      (node (ref "IC10") (pin "6") (pinfunction "OUT_6") (pintype "output"))
      (node (ref "R21") (pin "1") (pinfunction "1_1") (pintype "passive"))
    )
    (net (code "41") (name "Net-(R10-Pad2)") (class "Default")
      (node (ref "R10") (pin "2") (pinfunction "2_2") (pintype "passive"))
      (node (ref "R11") (pin "1") (pinfunction "1_1") (pintype "passive"))
      (node (ref "T2") (pin "B") (pinfunction "B_B") (pintype "passive"))
    )
    (net (code "42") (name "Net-(R13-Pad1)") (class "Default")
      (node (ref "R13") (pin "1") (pinfunction "1_1") (pintype "passive"))
      (node (ref "T2") (pin "E") (pinfunction "E_E") (pintype "passive"))
    )
    (net (code "43") (name "Net-(R16-Pad2)") (class "Default")
      (node (ref "R16") (pin "2") (pinfunction "2_2") (pintype "passive"))
      (node (ref "R18") (pin "1") (pinfunction "1_1") (pintype "passive"))
    )
    (net (code "44") (name "Net-(X2A-S)") (class "Default")
      (node (ref "R2") (pin "2") (pinfunction "2_2") (pintype "passive"))
      (node (ref "R4") (pin "1") (pinfunction "1_1") (pintype "passive"))
      (node (ref "X2") (pin "1") (pinfunction "S_1") (pintype "passive"))
    )
    (net (code "45") (name "Net-(X3A-S)") (class "Default")
      (node (ref "R5") (pin "2") (pinfunction "2_2") (pintype "passive"))
      (node (ref "X3") (pin "1") (pinfunction "S_1") (pintype "passive"))
    )
    (net (code "46") (name "Net-(X8A-S)") (class "Default")
      (node (ref "R9") (pin "1") (pinfunction "1_1") (pintype "passive"))
      (node (ref "X8") (pin "1") (pinfunction "S_1") (pintype "passive"))
    )
    (net (code "47") (name "Net-(X9A-S)") (class "Default")
      (node (ref "R14") (pin "1") (pinfunction "1_1") (pintype "passive"))
      (node (ref "X9") (pin "1") (pinfunction "S_1") (pintype "passive"))
    )
    (net (code "48") (name "Net-(X9B-S)") (class "Default")
      (node (ref "R15") (pin "1") (pinfunction "1_1") (pintype "passive"))
      (node (ref "X9") (pin "2") (pinfunction "S_2") (pintype "passive"))
    )
    (net (code "49") (name "Net-(X10A-S)") (class "Default")
      (node (ref "R21") (pin "2") (pinfunction "2_2") (pintype "passive"))
      (node (ref "X10") (pin "1") (pinfunction "S_1") (pintype "passive"))
    )
    (net (code "50") (name "unconnected-(IC2-VADJ-Pad3)") (class "Default")
      (node (ref "IC2") (pin "3") (pinfunction "VADJ_3") (pintype "bidirectional"))
    )
    (net (code "51") (name "unconnected-(IC2-VOA-Pad16)") (class "Default")
      (node (ref "IC2") (pin "16") (pinfunction "VOA_16") (pintype "bidirectional"))
    )
    (net (code "52") (name "unconnected-(IC10-BW-Pad1)") (class "Default")
      (node (ref "IC10") (pin "1") (pinfunction "BW_1") (pintype "passive"))
    )
  )
)
